# tricorder-featherwing-mk-1_0.net
KiCad netlist of a schematic drawn in EAGLE
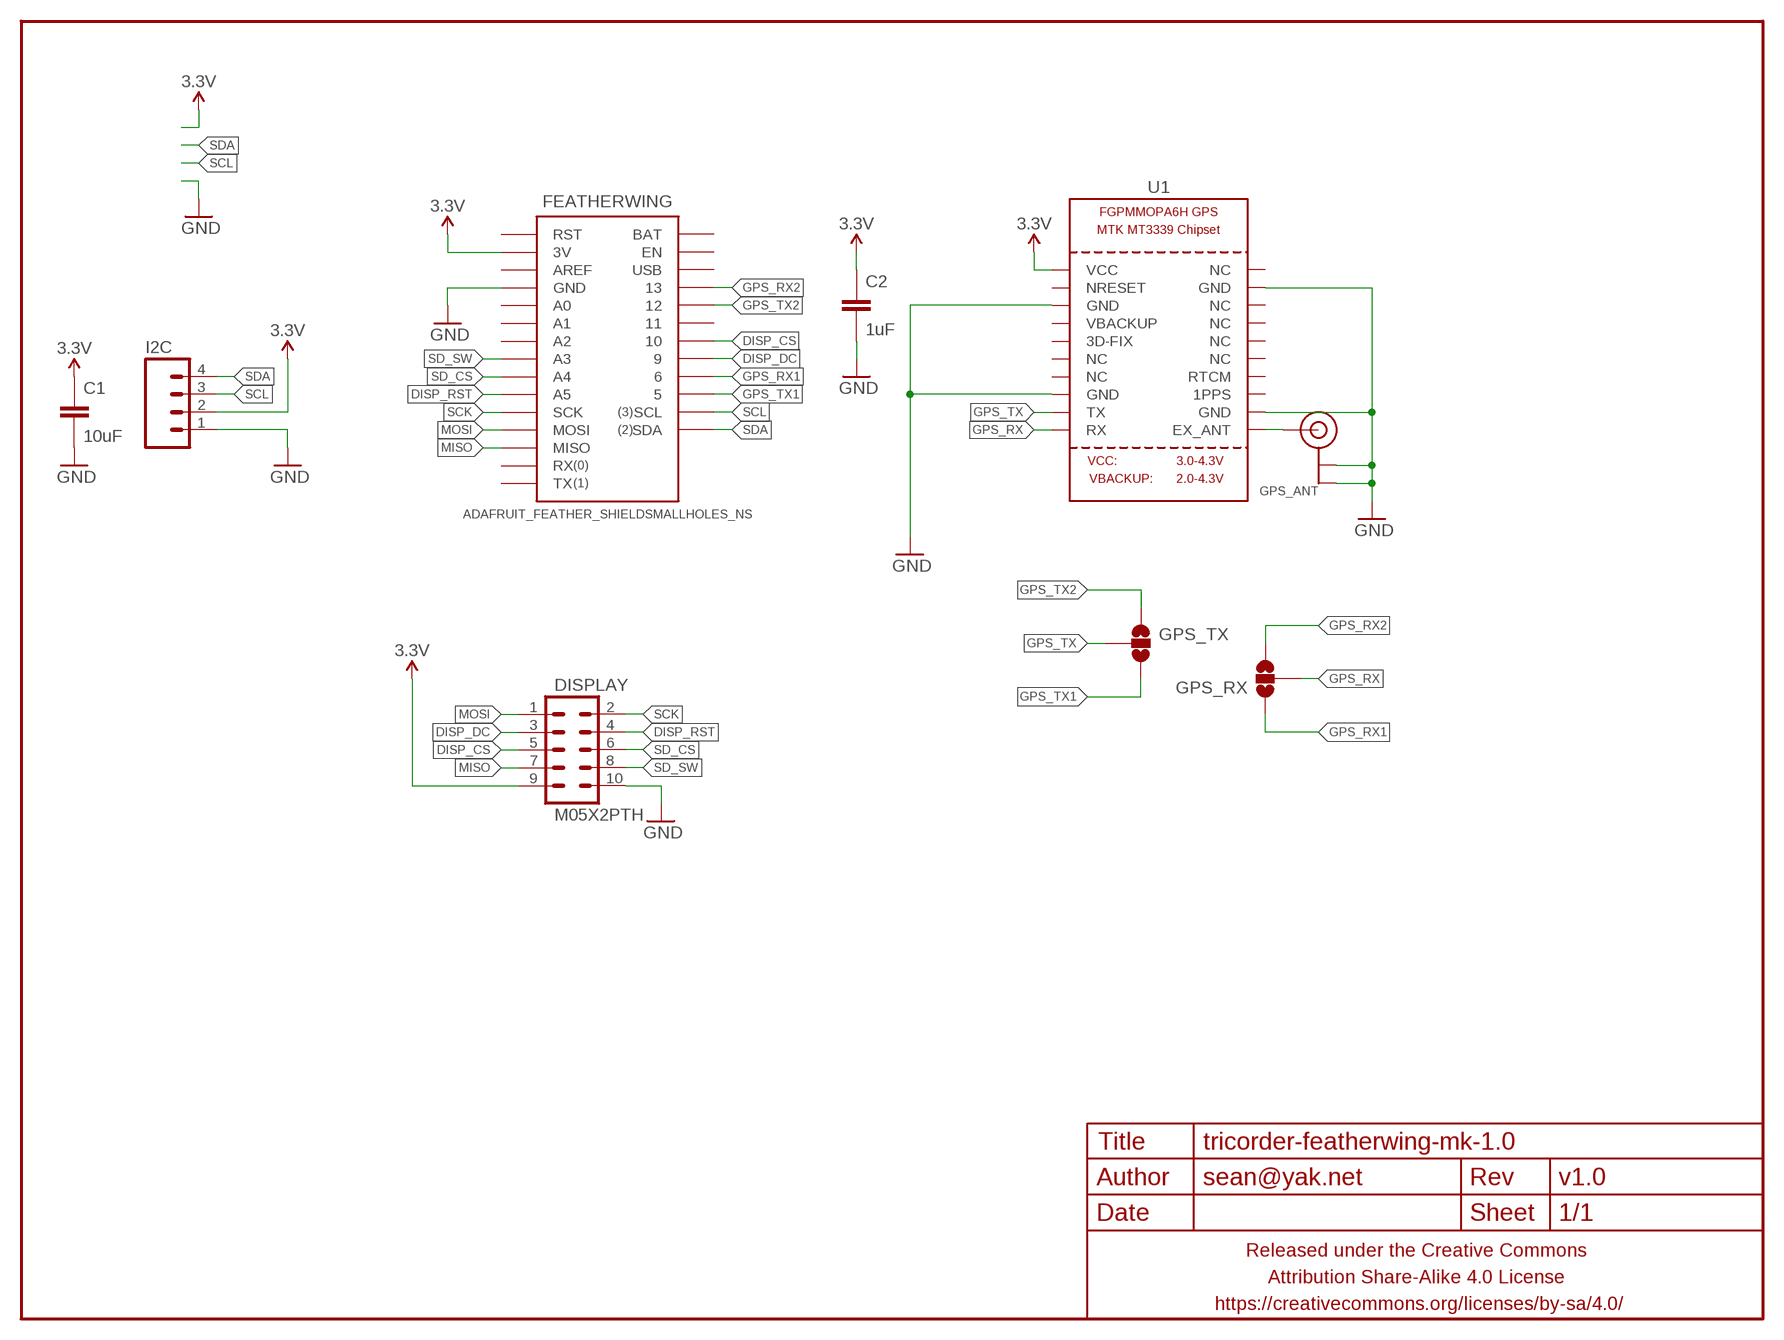
[diagram p0: schematic, sheet 1]

(export (version "E")
  (design (tool "Eeschema 10.0.6"))
  (components
    (comp (ref "C1")
      (value "10uF")
      (footprint "eagle-import:C1210")
      (libsource (lib "eagle-import") (part "CAPACITOR-CERAMICC1210"))
    )
    (comp (ref "C2")
      (value "1uF")
      (footprint "eagle-import:C0603")
      (libsource (lib "eagle-import") (part "CAPACITOR-CERAMICC0603"))
    )
    (comp (ref "DISPLAY")
      (value "M05X2PTH")
      (footprint "eagle-import:AVR_ICSP")
      (libsource (lib "eagle-import") (part "M05X2PTH"))
    )
    (comp (ref "FEATHERWING")
      (value "ADAFRUIT_FEATHER_SHIELDSMALLHOLES_NS")
      (footprint "eagle-import:ADAFRUIT_FEATHER_SMALLHOLES_NS")
      (libsource (lib "eagle-import") (part "ADAFRUIT_FEATHER_SHIELDSMALLHOLES_NS"))
    )
    (comp (ref "FRAME1")
      (value "FRAME-LETTERNO_PACKAGE")
      (footprint "eagle-import:DUMMY")
      (fields (field (name "DESIGNER") "sean@yak.net") (field (name "VERSION") "v1.0"))
      (libsource (lib "eagle-import") (part "FRAME-LETTERNO_PACKAGE"))
    )
    (comp (ref "GPS_ANT")
      (value "ANTENNA_U.FL")
      (footprint "eagle-import:U.FL")
      (libsource (lib "eagle-import") (part "ANTENNA_U.FL"))
    )
    (comp (ref "GPS_RX")
      (value "JUMPER-PAD-3-NOFULL_BOX_SILK")
      (footprint "eagle-import:PAD-JUMPER-3-NO_YES_SILK_FULL_BOX")
      (libsource (lib "eagle-import") (part "JUMPER-PAD-3-NOFULL_BOX_SILK"))
    )
    (comp (ref "GPS_TX")
      (value "JUMPER-PAD-3-NOFULL_BOX_SILK")
      (footprint "eagle-import:PAD-JUMPER-3-NO_YES_SILK_FULL_BOX")
      (libsource (lib "eagle-import") (part "JUMPER-PAD-3-NOFULL_BOX_SILK"))
    )
    (comp (ref "I2C")
      (value "M04PTH")
      (footprint "eagle-import:1X04-PTH-VERT")
      (libsource (lib "eagle-import") (part "M04PTH"))
    )
    (comp (ref "U1")
      (value "GPS_FGPMMOPA6H")
      (footprint "eagle-import:FGPMMOPA6H")
      (libsource (lib "eagle-import") (part "GPS_FGPMMOPA6H"))
    )
  )
  (nets
    (net (code "1") (name "3.3V") (class "Default")
      (node (ref "C1") (pin "1") (pinfunction "1_1") (pintype "passive"))
      (node (ref "C2") (pin "1") (pinfunction "1_1") (pintype "passive"))
      (node (ref "DISPLAY") (pin "9") (pinfunction "9_9") (pintype "passive"))
      (node (ref "FEATHERWING") (pin "3V") (pinfunction "3V_3V") (pintype "bidirectional"))
      (node (ref "I2C") (pin "2") (pinfunction "2_2") (pintype "passive"))
      (node (ref "U1") (pin "P$1") (pinfunction "VCC_P$1") (pintype "bidirectional"))
    )
    (net (code "2") (name "DISP_CS") (class "Default")
      (node (ref "DISPLAY") (pin "5") (pinfunction "5_5") (pintype "passive"))
      (node (ref "FEATHERWING") (pin "10") (pinfunction "10_10") (pintype "bidirectional"))
    )
    (net (code "3") (name "DISP_DC") (class "Default")
      (node (ref "DISPLAY") (pin "3") (pinfunction "3_3") (pintype "passive"))
      (node (ref "FEATHERWING") (pin "9") (pinfunction "9_9") (pintype "bidirectional"))
    )
    (net (code "4") (name "DISP_RST") (class "Default")
      (node (ref "DISPLAY") (pin "4") (pinfunction "4_4") (pintype "passive"))
      (node (ref "FEATHERWING") (pin "A5") (pinfunction "A5_A5") (pintype "bidirectional"))
    )
    (net (code "5") (name "GND") (class "Default")
      (node (ref "C1") (pin "2") (pinfunction "2_2") (pintype "passive"))
      (node (ref "C2") (pin "2") (pinfunction "2_2") (pintype "passive"))
      (node (ref "DISPLAY") (pin "10") (pinfunction "10_10") (pintype "passive"))
      (node (ref "FEATHERWING") (pin "GND@0") (pinfunction "GND_GND@0") (pintype "bidirectional"))
      (node (ref "FEATHERWING") (pin "GND@1") (pinfunction "GND_GND@1") (pintype "bidirectional"))
      (node (ref "GPS_ANT") (pin "1") (pinfunction "GND_1") (pintype "passive"))
      (node (ref "GPS_ANT") (pin "2") (pinfunction "GND_2") (pintype "passive"))
      (node (ref "I2C") (pin "1") (pinfunction "1_1") (pintype "passive"))
      (node (ref "U1") (pin "P$12") (pinfunction "GND_P$12") (pintype "bidirectional"))
      (node (ref "U1") (pin "P$19") (pinfunction "GND_P$19") (pintype "bidirectional"))
      (node (ref "U1") (pin "P$3") (pinfunction "GND_P$3") (pintype "bidirectional"))
      (node (ref "U1") (pin "P$8") (pinfunction "GND_P$8") (pintype "bidirectional"))
    )
    (net (code "6") (name "GPS_RX") (class "Default")
      (node (ref "GPS_RX") (pin "2") (pinfunction "2_2") (pintype "passive"))
      (node (ref "U1") (pin "P$10") (pinfunction "RX_P$10") (pintype "bidirectional"))
    )
    (net (code "7") (name "GPS_RX1") (class "Default")
      (node (ref "FEATHERWING") (pin "6") (pinfunction "6_6") (pintype "bidirectional"))
      (node (ref "GPS_RX") (pin "1") (pinfunction "1_1") (pintype "passive"))
    )
    (net (code "8") (name "GPS_RX2") (class "Default")
      (node (ref "FEATHERWING") (pin "13") (pinfunction "13_13") (pintype "bidirectional"))
      (node (ref "GPS_RX") (pin "3") (pinfunction "3_3") (pintype "passive"))
    )
    (net (code "9") (name "GPS_TX") (class "Default")
      (node (ref "GPS_TX") (pin "2") (pinfunction "2_2") (pintype "passive"))
      (node (ref "U1") (pin "P$9") (pinfunction "TX_P$9") (pintype "bidirectional"))
    )
    (net (code "10") (name "GPS_TX1") (class "Default")
      (node (ref "FEATHERWING") (pin "5") (pinfunction "5_5") (pintype "bidirectional"))
      (node (ref "GPS_TX") (pin "3") (pinfunction "3_3") (pintype "passive"))
    )
    (net (code "11") (name "GPS_TX2") (class "Default")
      (node (ref "FEATHERWING") (pin "12") (pinfunction "12_12") (pintype "bidirectional"))
      (node (ref "GPS_TX") (pin "1") (pinfunction "1_1") (pintype "passive"))
    )
    (net (code "12") (name "MISO") (class "Default")
      (node (ref "DISPLAY") (pin "7") (pinfunction "7_7") (pintype "passive"))
      (node (ref "FEATHERWING") (pin "MISO") (pinfunction "MISO_MISO") (pintype "bidirectional"))
    )
    (net (code "13") (name "MOSI") (class "Default")
      (node (ref "DISPLAY") (pin "1") (pinfunction "1_1") (pintype "passive"))
      (node (ref "FEATHERWING") (pin "MOSI") (pinfunction "MOSI_MOSI") (pintype "bidirectional"))
    )
    (net (code "14") (name "Net-(GPS_ANT-SIGNAL)") (class "Default")
      (node (ref "GPS_ANT") (pin "3") (pinfunction "SIGNAL_3") (pintype "passive"))
      (node (ref "U1") (pin "P$11") (pinfunction "EX_ANT_P$11") (pintype "bidirectional"))
    )
    (net (code "15") (name "SCK") (class "Default")
      (node (ref "DISPLAY") (pin "2") (pinfunction "2_2") (pintype "passive"))
      (node (ref "FEATHERWING") (pin "SCK") (pinfunction "SCK_SCK") (pintype "bidirectional"))
    )
    (net (code "16") (name "SCL") (class "Default")
      (node (ref "FEATHERWING") (pin "SCL") (pinfunction "SCL_SCL") (pintype "bidirectional"))
      (node (ref "I2C") (pin "3") (pinfunction "3_3") (pintype "passive"))
    )
    (net (code "17") (name "SDA") (class "Default")
      (node (ref "FEATHERWING") (pin "SDA") (pinfunction "SDA_SDA") (pintype "bidirectional"))
      (node (ref "I2C") (pin "4") (pinfunction "4_4") (pintype "passive"))
    )
    (net (code "18") (name "SD_CS") (class "Default")
      (node (ref "DISPLAY") (pin "6") (pinfunction "6_6") (pintype "passive"))
      (node (ref "FEATHERWING") (pin "A4") (pinfunction "A4_A4") (pintype "bidirectional"))
    )
    (net (code "19") (name "SD_SW") (class "Default")
      (node (ref "DISPLAY") (pin "8") (pinfunction "8_8") (pintype "passive"))
      (node (ref "FEATHERWING") (pin "A3") (pinfunction "A3_A3") (pintype "bidirectional"))
    )
    (net (code "20") (name "unconnected-(FEATHERWING-Pad11)") (class "Default")
      (node (ref "FEATHERWING") (pin "11") (pinfunction "11_11") (pintype "bidirectional"))
    )
    (net (code "21") (name "unconnected-(FEATHERWING-PadA0)") (class "Default")
      (node (ref "FEATHERWING") (pin "A0") (pinfunction "A0_A0") (pintype "bidirectional"))
    )
    (net (code "22") (name "unconnected-(FEATHERWING-PadA1)") (class "Default")
      (node (ref "FEATHERWING") (pin "A1") (pinfunction "A1_A1") (pintype "bidirectional"))
    )
    (net (code "23") (name "unconnected-(FEATHERWING-PadA2)") (class "Default")
      (node (ref "FEATHERWING") (pin "A2") (pinfunction "A2_A2") (pintype "bidirectional"))
    )
    (net (code "24") (name "unconnected-(FEATHERWING-PadAREF)") (class "Default")
      (node (ref "FEATHERWING") (pin "AREF") (pinfunction "AREF_AREF") (pintype "bidirectional"))
    )
    (net (code "25") (name "unconnected-(FEATHERWING-PadBAT)") (class "Default")
      (node (ref "FEATHERWING") (pin "BAT") (pinfunction "BAT_BAT") (pintype "bidirectional"))
    )
    (net (code "26") (name "unconnected-(FEATHERWING-PadEN)") (class "Default")
      (node (ref "FEATHERWING") (pin "EN") (pinfunction "EN_EN") (pintype "bidirectional"))
    )
    (net (code "27") (name "unconnected-(FEATHERWING-PadRST)") (class "Default")
      (node (ref "FEATHERWING") (pin "RST") (pinfunction "RST_RST") (pintype "bidirectional"))
    )
    (net (code "28") (name "unconnected-(FEATHERWING-PadRX)") (class "Default")
      (node (ref "FEATHERWING") (pin "RX") (pinfunction "RX_RX") (pintype "bidirectional"))
    )
    (net (code "29") (name "unconnected-(FEATHERWING-PadTX)") (class "Default")
      (node (ref "FEATHERWING") (pin "TX") (pinfunction "TX_TX") (pintype "bidirectional"))
    )
    (net (code "30") (name "unconnected-(FEATHERWING-PadUSB)") (class "Default")
      (node (ref "FEATHERWING") (pin "USB") (pinfunction "USB_USB") (pintype "bidirectional"))
    )
    (net (code "31") (name "unconnected-(U1-1PPS-PadP$13)") (class "Default")
      (node (ref "U1") (pin "P$13") (pinfunction "1PPS_P$13") (pintype "bidirectional"))
    )
    (net (code "32") (name "unconnected-(U1-3D-FIX-PadP$5)") (class "Default")
      (node (ref "U1") (pin "P$5") (pinfunction "3D-FIX_P$5") (pintype "bidirectional"))
    )
    (net (code "33") (name "unconnected-(U1-NC-PadP$6)") (class "Default")
      (node (ref "U1") (pin "P$6") (pinfunction "NC_P$6") (pintype "bidirectional"))
    )
    (net (code "34") (name "unconnected-(U1-NC-PadP$7)") (class "Default")
      (node (ref "U1") (pin "P$7") (pinfunction "NC_P$7") (pintype "bidirectional"))
    )
    (net (code "35") (name "unconnected-(U1-NC-PadP$15)") (class "Default")
      (node (ref "U1") (pin "P$15") (pinfunction "NC_P$15") (pintype "bidirectional"))
    )
    (net (code "36") (name "unconnected-(U1-NC-PadP$16)") (class "Default")
      (node (ref "U1") (pin "P$16") (pinfunction "NC_P$16") (pintype "bidirectional"))
    )
    (net (code "37") (name "unconnected-(U1-NC-PadP$17)") (class "Default")
      (node (ref "U1") (pin "P$17") (pinfunction "NC_P$17") (pintype "bidirectional"))
    )
    (net (code "38") (name "unconnected-(U1-NC-PadP$18)") (class "Default")
      (node (ref "U1") (pin "P$18") (pinfunction "NC_P$18") (pintype "bidirectional"))
    )
    (net (code "39") (name "unconnected-(U1-NC-PadP$20)") (class "Default")
      (node (ref "U1") (pin "P$20") (pinfunction "NC_P$20") (pintype "bidirectional"))
    )
    (net (code "40") (name "unconnected-(U1-NRESET-PadP$2)") (class "Default")
      (node (ref "U1") (pin "P$2") (pinfunction "NRESET_P$2") (pintype "bidirectional"))
    )
    (net (code "41") (name "unconnected-(U1-RTCM-PadP$14)") (class "Default")
      (node (ref "U1") (pin "P$14") (pinfunction "RTCM_P$14") (pintype "bidirectional"))
    )
    (net (code "42") (name "unconnected-(U1-VBACKUP-PadP$4)") (class "Default")
      (node (ref "U1") (pin "P$4") (pinfunction "VBACKUP_P$4") (pintype "bidirectional"))
    )
  )
)
